# SCH_mylm317_2023-06-13.net
KiCad netlist of a schematic drawn in EasyEDA
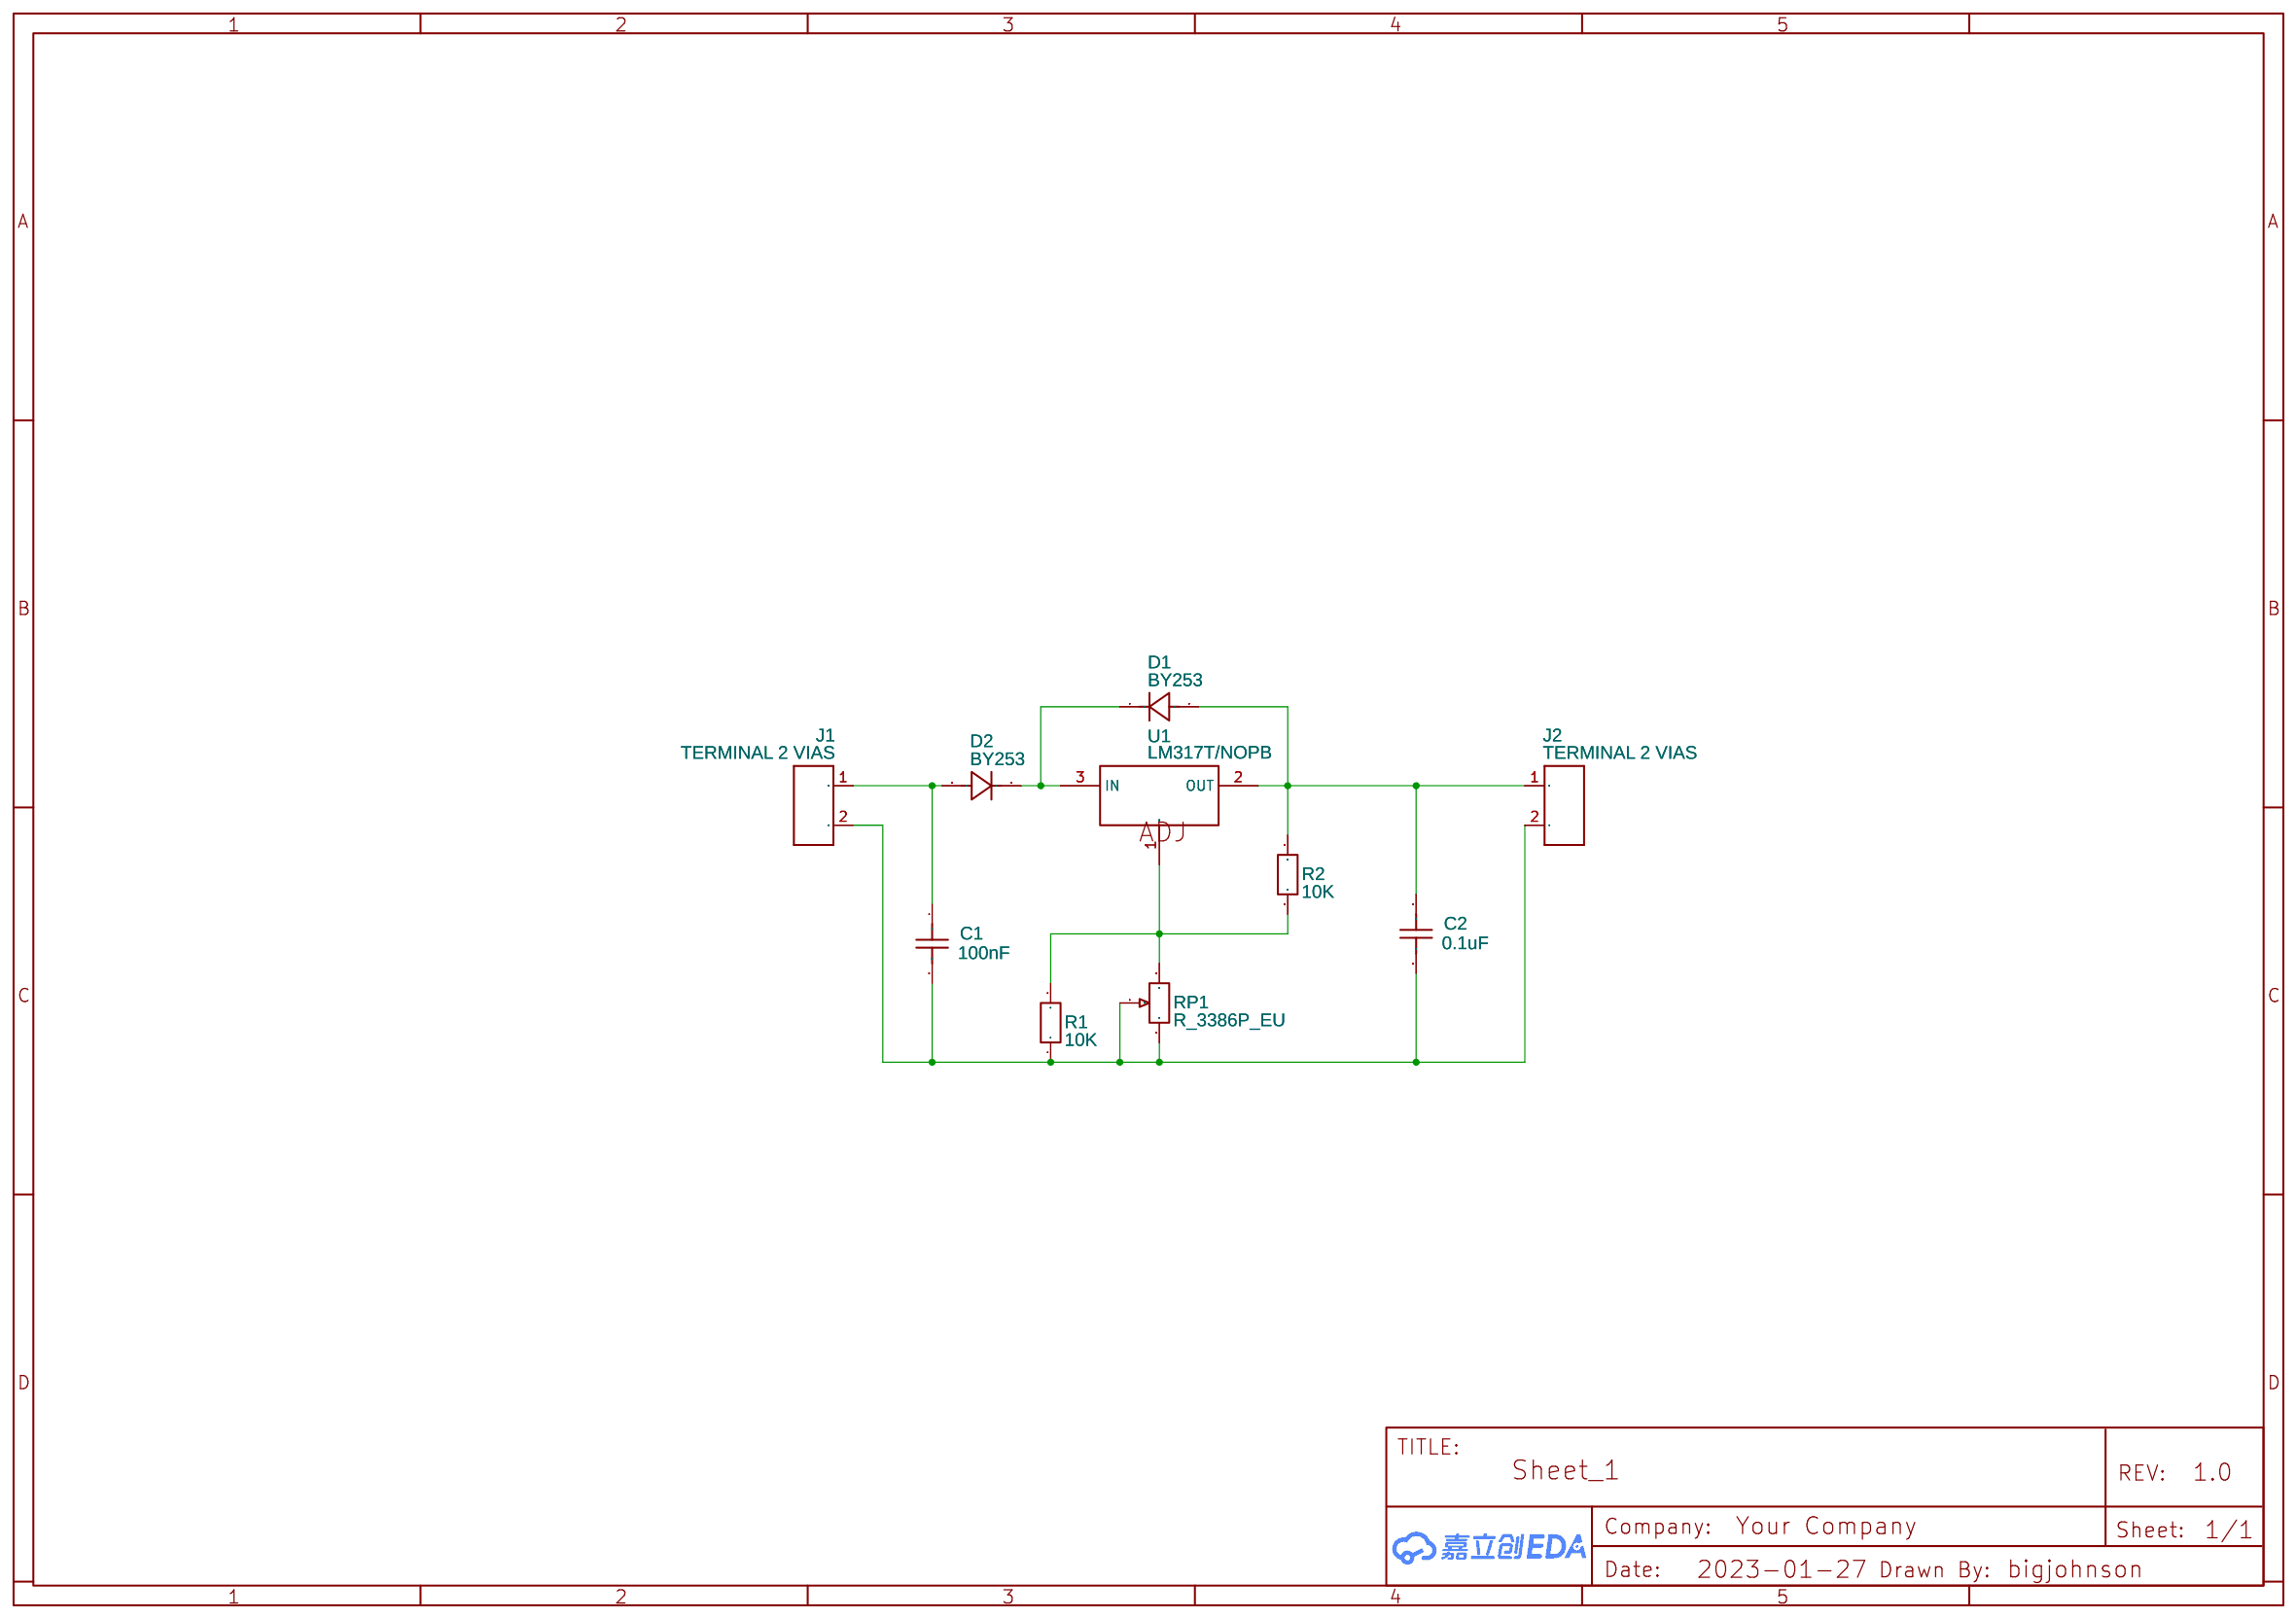
[diagram p0: schematic sheet]

(export (version "E")
  (design (tool "Eeschema 10.0.6"))
  (components
    (comp (ref "C1")
      (value "100nF")
      (fields
        (field (name "BOM_Manufacturer Part") "CT4-0805B103 K500")
        (field (name "BOM_Supplier Part") "C8033")
      )
      (libsource (lib "") (part "CT4-0805B103 K500"))
    )
    (comp (ref "C2")
      (value "0.1uF")
      (fields
        (field (name "BOM_Manufacturer Part") "CT4-0805B103 K500")
        (field (name "BOM_Supplier Part") "C8033")
      )
      (libsource (lib "") (part "CT4-0805B103 K500"))
    )
    (comp (ref "D1")
      (value "BY253")
      (fields (field (name "BOM_Manufacturer Part") "MUR460") (field (name "BOM_Supplier Part") "C2990844"))
      (libsource (lib "") (part "MUR460_C2990844_1"))
    )
    (comp (ref "D2")
      (value "BY253")
      (fields (field (name "BOM_Manufacturer Part") "MUR460") (field (name "BOM_Supplier Part") "C2990844"))
      (libsource (lib "") (part "MUR460_C2990844"))
    )
    (comp (ref "J1")
      (value "TERMINAL 2 VIAS")
      (fields (field (name "BOM_Manufacturer Part") "GS009S-2P-2"))
      (libsource (lib "") (part "TERMINAL 2 VIAS_1"))
    )
    (comp (ref "J2")
      (value "TERMINAL 2 VIAS")
      (fields (field (name "BOM_Manufacturer Part") "GS009S-2P-2"))
      (libsource (lib "") (part "TERMINAL 2 VIAS"))
    )
    (comp (ref "R1") (value "10K") (libsource (lib "") (part "Res_AXIAL-0.4(1/4W)_EU")))
    (comp (ref "R2") (value "10K") (libsource (lib "") (part "Res_AXIAL-0.4(1/4W)_EU")))
    (comp (ref "RP1") (value "R_3386P_EU") (libsource (lib "") (part "R_3386P_EU")))
    (comp (ref "U1")
      (value "LM317T/NOPB")
      (fields (field (name "BOM_Supplier Part") "C2870516"))
      (libsource (lib "") (part "LM317T/NOPB"))
    )
  )
  (nets
    (net (code "1") (name "Net-(C1-Pad2)") (class "Default")
      (node (ref "C1") (pin "2") (pinfunction "2_2") (pintype "unspecified"))
      (node (ref "C2") (pin "2") (pinfunction "2_2") (pintype "unspecified"))
      (node (ref "J1") (pin "2") (pinfunction "2_2") (pintype "unspecified"))
      (node (ref "J2") (pin "2") (pinfunction "2_2") (pintype "unspecified"))
      (node (ref "R1") (pin "1") (pinfunction "1_1") (pintype "unspecified"))
      (node (ref "RP1") (pin "1") (pinfunction "1_1") (pintype "input"))
      (node (ref "RP1") (pin "2") (pinfunction "2_2") (pintype "input"))
    )
    (net (code "2") (name "Net-(D1-A)") (class "Default")
      (node (ref "C2") (pin "1") (pinfunction "1_1") (pintype "unspecified"))
      (node (ref "D1") (pin "2") (pinfunction "A_2") (pintype "unspecified"))
      (node (ref "J2") (pin "1") (pinfunction "1_1") (pintype "unspecified"))
      (node (ref "R2") (pin "2") (pinfunction "2_2") (pintype "unspecified"))
      (node (ref "U1") (pin "2") (pinfunction "OUT_2") (pintype "passive"))
    )
    (net (code "3") (name "Net-(D1-K)") (class "Default")
      (node (ref "D1") (pin "1") (pinfunction "K_1") (pintype "unspecified"))
      (node (ref "D2") (pin "1") (pinfunction "K_1") (pintype "unspecified"))
      (node (ref "U1") (pin "3") (pinfunction "IN_3") (pintype "passive"))
    )
    (net (code "4") (name "Net-(D2-A)") (class "Default")
      (node (ref "C1") (pin "1") (pinfunction "1_1") (pintype "unspecified"))
      (node (ref "D2") (pin "2") (pinfunction "A_2") (pintype "unspecified"))
      (node (ref "J1") (pin "1") (pinfunction "1_1") (pintype "unspecified"))
    )
    (net (code "5") (name "Net-(U1-ADJ)") (class "Default")
      (node (ref "R1") (pin "2") (pinfunction "2_2") (pintype "unspecified"))
      (node (ref "R2") (pin "1") (pinfunction "1_1") (pintype "unspecified"))
      (node (ref "RP1") (pin "3") (pinfunction "3_3") (pintype "input"))
      (node (ref "U1") (pin "1") (pinfunction "ADJ_1") (pintype "passive"))
    )
  )
)
